# CT310_V1_1.net
KiCad netlist of a schematic drawn in Altium Designer
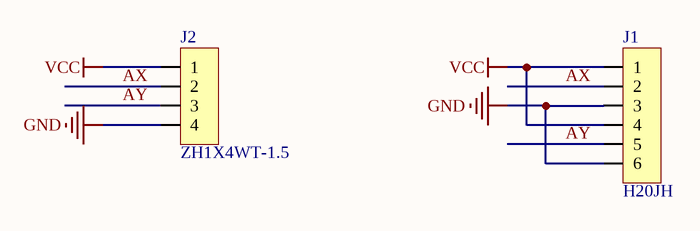
[diagram p0: CT310高端控制盒左摇杆电路V1.1.SchDoc]

(export (version "E")
  (design (tool "Eeschema 10.0.6"))
  (components
    (comp (ref "J1")
      (value "H20JH")
      (footprint "H20JH")
      (libsource (lib "Connector Class") (part "HEADER1X6"))
    )
    (comp (ref "J2")
      (value "ZH1X4WT-1.5")
      (footprint "ZH1X4WT-1.5")
      (libsource (lib "Connector Class") (part "HEADER1X4"))
    )
  )
  (nets
    (net (code "1") (name "/AX") (class "Default")
      (node (ref "J1") (pin "2") (pinfunction "2_2") (pintype "passive"))
      (node (ref "J2") (pin "2") (pinfunction "2_2") (pintype "passive"))
    )
    (net (code "2") (name "/AY") (class "Default")
      (node (ref "J1") (pin "5") (pinfunction "5_5") (pintype "passive"))
      (node (ref "J2") (pin "3") (pinfunction "3_3") (pintype "passive"))
    )
    (net (code "3") (name "GND") (class "Default")
      (node (ref "J1") (pin "3") (pinfunction "3_3") (pintype "passive"))
      (node (ref "J1") (pin "6") (pinfunction "6_6") (pintype "passive"))
      (node (ref "J2") (pin "4") (pinfunction "4_4") (pintype "passive"))
    )
    (net (code "4") (name "VCC") (class "Default")
      (node (ref "J1") (pin "1") (pinfunction "1_1") (pintype "passive"))
      (node (ref "J1") (pin "4") (pinfunction "4_4") (pintype "passive"))
      (node (ref "J2") (pin "1") (pinfunction "1_1") (pintype "passive"))
    )
  )
)
